# N2onboardTelemetry.net
KiCad netlist of a schematic drawn in EasyEDA
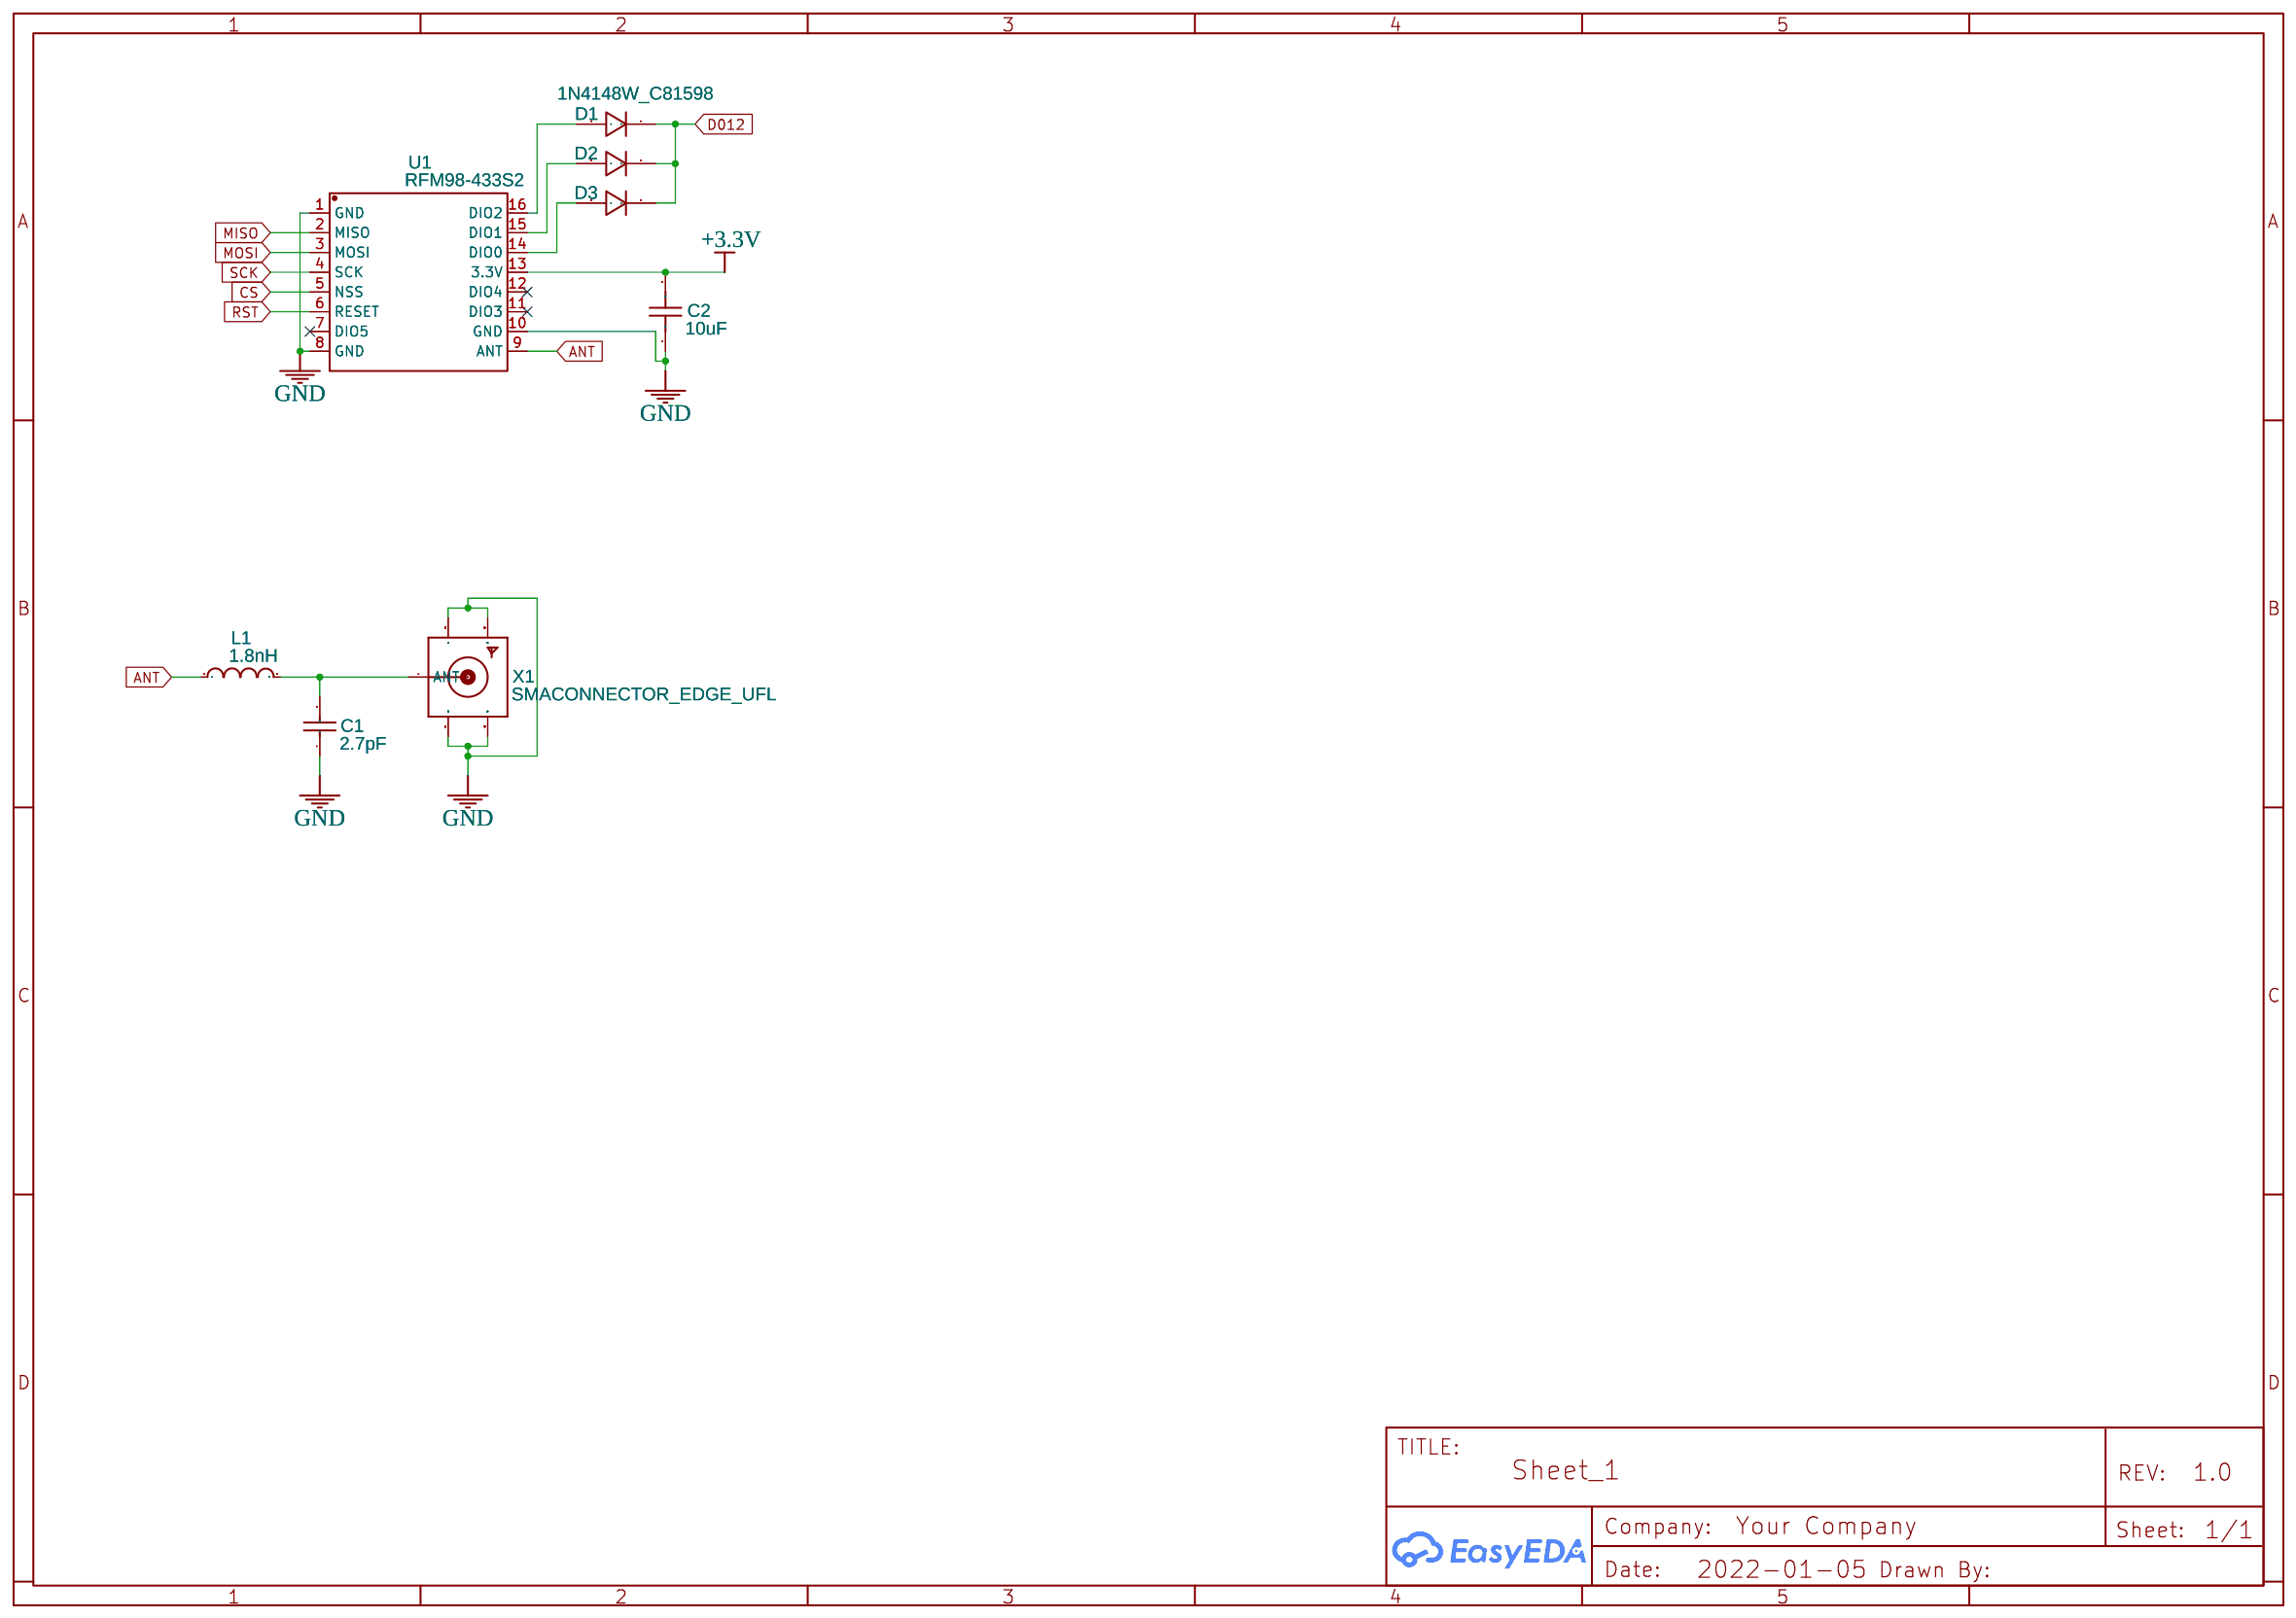
[diagram p0: schematic sheet]

(export (version "E")
  (design (tool "Eeschema 10.0.6"))
  (components
    (comp (ref "C1")
      (value "2.7pF")
      (fields
        (field (name "BOM_Manufacturer Part") "0402CG2R7C500NT")
        (field (name "BOM_Supplier Part") "C1561")
      )
      (libsource (lib "") (part "0402CG2R7C500NT"))
    )
    (comp (ref "C2")
      (value "10uF")
      (fields
        (field (name "BOM_Manufacturer Part") "CL10A106KP8NNNC")
        (field (name "BOM_Supplier Part") "C19702")
      )
      (libsource (lib "") (part "CL10A106KP8NNNC"))
    )
    (comp (ref "D1")
      (value "1N4148W_C81598")
      (fields (field (name "BOM_Manufacturer Part") "1N4148W") (field (name "BOM_Supplier Part") "C81598"))
      (libsource (lib "") (part "1N4148W_C81598"))
    )
    (comp (ref "D2")
      (value "1N4148W_C81598")
      (fields (field (name "BOM_Manufacturer Part") "1N4148W") (field (name "BOM_Supplier Part") "C81598"))
      (libsource (lib "") (part "1N4148W_C81598"))
    )
    (comp (ref "D3")
      (value "1N4148W_C81598")
      (fields (field (name "BOM_Manufacturer Part") "1N4148W") (field (name "BOM_Supplier Part") "C81598"))
      (libsource (lib "") (part "1N4148W_C81598"))
    )
    (comp (ref "L1")
      (value "1.8nH")
      (fields
        (field (name "BOM_Manufacturer Part") "HK10051N8S-T")
        (field (name "BOM_Supplier Part") "C89157")
      )
      (libsource (lib "") (part "HK10051N8S-T"))
    )
    (comp (ref "U1")
      (value "RFM98-433S2")
      (fields (field (name "BOM_Supplier Part") "C171661"))
      (libsource (lib "") (part "RFM98-433S2"))
    )
    (comp (ref "X1") (value "SMACONNECTOR_EDGE_UFL") (libsource (lib "") (part "SMACONNECTOR_EDGE_UFL")))
  )
  (nets
    (net (code "1") (name "+3.3V") (class "Default")
      (node (ref "C2") (pin "2") (pinfunction "2_2") (pintype "unspecified"))
      (node (ref "U1") (pin "13") (pinfunction "3.3V_13") (pintype "unspecified"))
    )
    (net (code "2") (name "ANT") (class "Default")
      (node (ref "L1") (pin "1") (pinfunction "1_1") (pintype "unspecified"))
      (node (ref "U1") (pin "9") (pinfunction "ANT_9") (pintype "unspecified"))
    )
    (net (code "3") (name "CS") (class "Default")
      (node (ref "U1") (pin "5") (pinfunction "NSS_5") (pintype "unspecified"))
    )
    (net (code "4") (name "D012") (class "Default")
      (node (ref "D1") (pin "1") (pinfunction "K_1") (pintype "unspecified"))
      (node (ref "D2") (pin "1") (pinfunction "K_1") (pintype "unspecified"))
      (node (ref "D3") (pin "1") (pinfunction "K_1") (pintype "unspecified"))
    )
    (net (code "5") (name "GND") (class "Default")
      (node (ref "C1") (pin "1") (pinfunction "1_1") (pintype "input"))
      (node (ref "C2") (pin "1") (pinfunction "1_1") (pintype "unspecified"))
      (node (ref "U1") (pin "1") (pinfunction "GND_1") (pintype "unspecified"))
      (node (ref "U1") (pin "10") (pinfunction "GND_10") (pintype "unspecified"))
      (node (ref "U1") (pin "8") (pinfunction "GND_8") (pintype "unspecified"))
      (node (ref "X1") (pin "GND@1") (pinfunction "GND1_GND@1") (pintype "passive"))
      (node (ref "X1") (pin "GND@2") (pinfunction "GND2_GND@2") (pintype "passive"))
      (node (ref "X1") (pin "GND@3") (pinfunction "GND3_GND@3") (pintype "passive"))
      (node (ref "X1") (pin "GND@4") (pinfunction "GND4_GND@4") (pintype "passive"))
    )
    (net (code "6") (name "MISO") (class "Default")
      (node (ref "U1") (pin "2") (pinfunction "MISO_2") (pintype "unspecified"))
    )
    (net (code "7") (name "MOSI") (class "Default")
      (node (ref "U1") (pin "3") (pinfunction "MOSI_3") (pintype "unspecified"))
    )
    (net (code "8") (name "Net-(D1-A)") (class "Default")
      (node (ref "D1") (pin "2") (pinfunction "A_2") (pintype "unspecified"))
      (node (ref "U1") (pin "16") (pinfunction "DIO2_16") (pintype "unspecified"))
    )
    (net (code "9") (name "Net-(D2-A)") (class "Default")
      (node (ref "D2") (pin "2") (pinfunction "A_2") (pintype "unspecified"))
      (node (ref "U1") (pin "15") (pinfunction "DIO1_15") (pintype "unspecified"))
    )
    (net (code "10") (name "Net-(D3-A)") (class "Default")
      (node (ref "D3") (pin "2") (pinfunction "A_2") (pintype "unspecified"))
      (node (ref "U1") (pin "14") (pinfunction "DIO0_14") (pintype "unspecified"))
    )
    (net (code "11") (name "Net-(X1-ANT)") (class "Default")
      (node (ref "C1") (pin "2") (pinfunction "2_2") (pintype "input"))
      (node (ref "L1") (pin "2") (pinfunction "2_2") (pintype "unspecified"))
      (node (ref "X1") (pin "P") (pinfunction "ANT_P") (pintype "unspecified"))
    )
    (net (code "12") (name "RST") (class "Default")
      (node (ref "U1") (pin "6") (pinfunction "RESET_6") (pintype "unspecified"))
    )
    (net (code "13") (name "SCK") (class "Default")
      (node (ref "U1") (pin "4") (pinfunction "SCK_4") (pintype "unspecified"))
    )
    (net (code "14") (name "unconnected-(U1-DIO3-Pad11)") (class "Default")
      (node (ref "U1") (pin "11") (pinfunction "DIO3_11") (pintype "unspecified+no_connect"))
    )
    (net (code "15") (name "unconnected-(U1-DIO4-Pad12)") (class "Default")
      (node (ref "U1") (pin "12") (pinfunction "DIO4_12") (pintype "unspecified+no_connect"))
    )
    (net (code "16") (name "unconnected-(U1-DIO5-Pad7)") (class "Default")
      (node (ref "U1") (pin "7") (pinfunction "DIO5_7") (pintype "unspecified+no_connect"))
    )
  )
)
